# LED_SW_BUT.net
KiCad netlist of a schematic drawn in Altium Designer
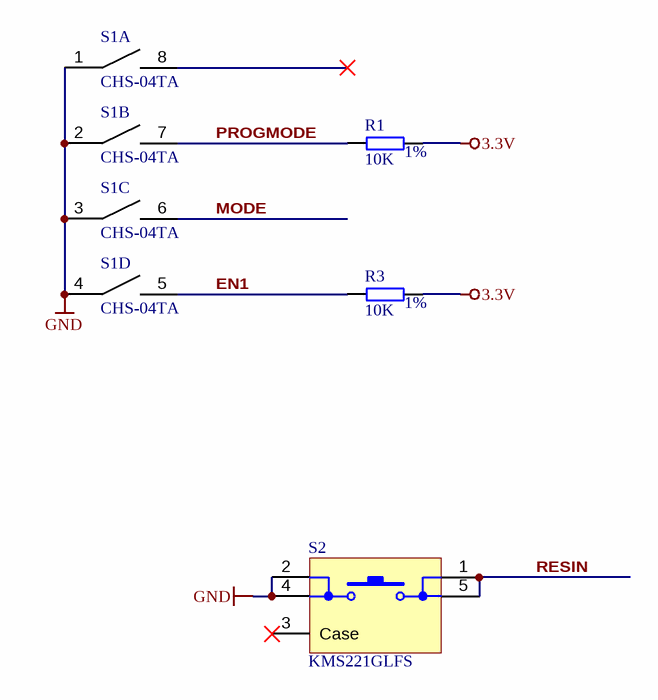
[diagram p0: LED_SW_BUT.SchDoc]

(export (version "E")
  (design (tool "Eeschema 10.0.6"))
  (components
    (comp (ref "R1")
      (value "10K")
      (footprint "RESC1005X40N")
      (description "WID SMD 10K 1% 0,063W")
      (fields (field (name "TOLERANCE") "1%"))
      (libsource (lib "TE") (part "RES"))
    )
    (comp (ref "R3")
      (value "10K")
      (footprint "RESC1005X40N")
      (description "WID SMD 10K 1% 0,063W")
      (fields (field (name "TOLERANCE") "1%"))
      (libsource (lib "TE") (part "RES"))
    )
    (comp (ref "S1")
      (value "CHS-04TA")
      (footprint "CHS-04TA")
      (description "DIP Schalter 4 fach 1,27mm SMD")
      (libsource (lib "TE") (part "CHS-04TA"))
    )
    (comp (ref "S2")
      (value "KMS221GLFS")
      (footprint "KMS2xxGLFS")
      (description "KMS221GLFS - SWITCH, SPST, 0.05A, 32VDC, SMD")
      (libsource (lib "TE") (part "KMS2xxGLFS"))
    )
  )
  (nets
    (net (code "1") (name "/EN1") (class "Default")
      (node (ref "R3") (pin "2") (pinfunction "2_2") (pintype "passive"))
      (node (ref "S1") (pin "5") (pinfunction "5_5") (pintype "passive"))
    )
    (net (code "2") (name "/MODE") (class "Default")
      (node (ref "S1") (pin "6") (pinfunction "6_6") (pintype "passive"))
    )
    (net (code "3") (name "/PROGMODE") (class "Default")
      (node (ref "R1") (pin "2") (pinfunction "2_2") (pintype "passive"))
      (node (ref "S1") (pin "7") (pinfunction "7_7") (pintype "passive"))
    )
    (net (code "4") (name "/RESIN") (class "Default")
      (node (ref "S2") (pin "1") (pinfunction "1_1") (pintype "passive"))
      (node (ref "S2") (pin "5") (pinfunction "5_5") (pintype "passive"))
    )
    (net (code "5") (name "3.3V") (class "Default")
      (node (ref "R1") (pin "1") (pinfunction "1_1") (pintype "passive"))
      (node (ref "R3") (pin "1") (pinfunction "1_1") (pintype "passive"))
    )
    (net (code "6") (name "GND") (class "Default")
      (node (ref "S1") (pin "1") (pinfunction "1_1") (pintype "passive"))
      (node (ref "S1") (pin "2") (pinfunction "2_2") (pintype "passive"))
      (node (ref "S1") (pin "3") (pinfunction "3_3") (pintype "passive"))
      (node (ref "S1") (pin "4") (pinfunction "4_4") (pintype "passive"))
      (node (ref "S2") (pin "2") (pinfunction "2_2") (pintype "passive"))
      (node (ref "S2") (pin "4") (pinfunction "4_4") (pintype "passive"))
    )
    (net (code "7") (name "unconnected-(S1-Pad8)") (class "Default")
      (node (ref "S1") (pin "8") (pinfunction "8_8") (pintype "passive+no_connect"))
    )
    (net (code "8") (name "unconnected-(S2-Case-Pad3)") (class "Default")
      (node (ref "S2") (pin "3") (pinfunction "Case_3") (pintype "passive+no_connect"))
    )
  )
)
